# SwipingCard.net
KiCad netlist of a schematic drawn in Altium Designer
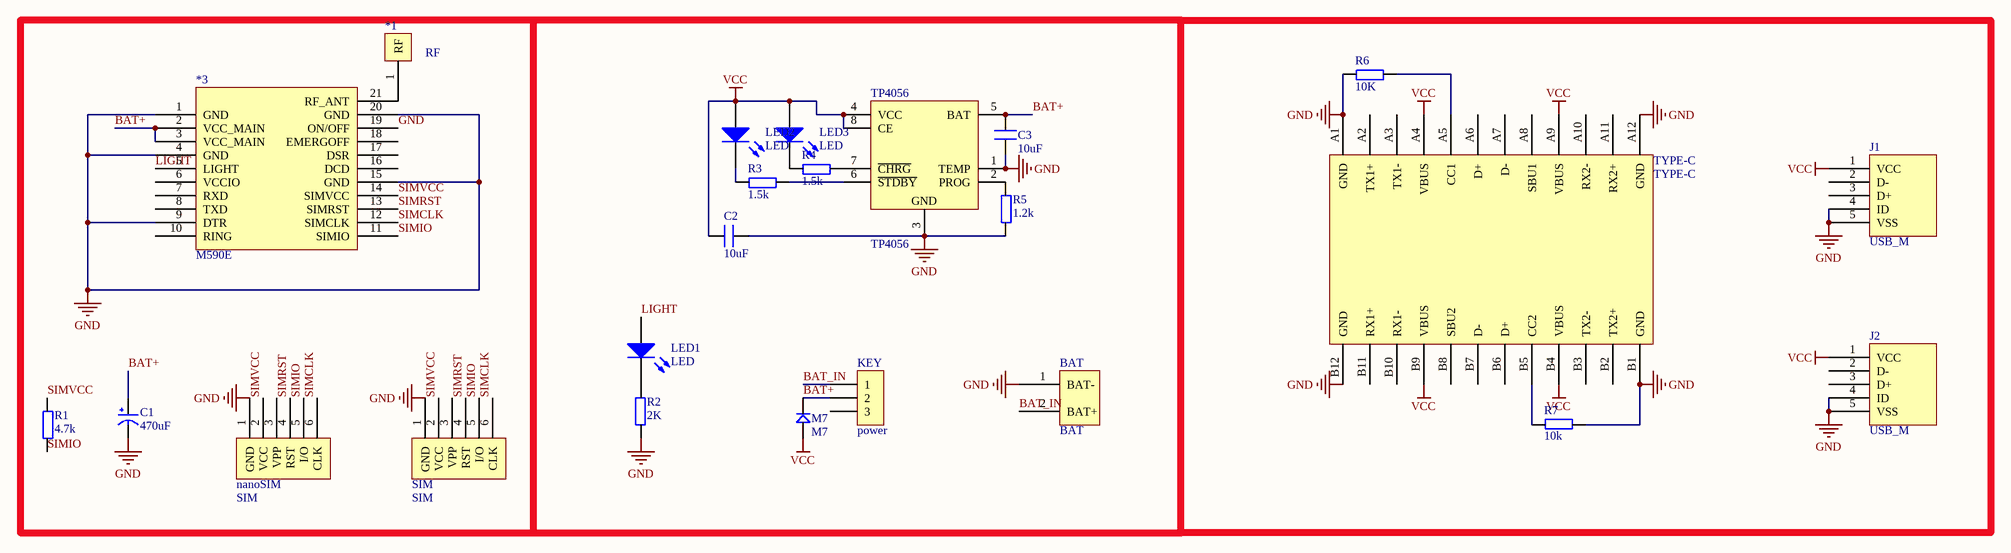
[diagram p0: SwipingCard.SchDoc]

(export (version "E")
  (design (tool "Eeschema 10.0.6"))
  (components
    (comp (ref "*1") (value "RF") (footprint "harder1x1") (libsource (lib "SwipingCard") (part "harder1x1")))
    (comp (ref "*3") (value "M590E") (footprint "M590E") (libsource (lib "SwipingCard") (part "M590E")))
    (comp (ref "BAT") (value "BAT") (footprint "HEADER1*2") (libsource (lib "SwipingCard") (part "BAT")))
    (comp (ref "C1") (value "470uF") (footprint "1206") (libsource (lib "SwipingCard") (part "C")))
    (comp (ref "C2") (value "10uF") (footprint "0603") (libsource (lib "SwipingCard") (part "cap")))
    (comp (ref "C3") (value "10uF") (footprint "0603") (libsource (lib "SwipingCard") (part "cap")))
    (comp (ref "J1")
      (value "USB_M")
      (footprint "USB_MICRO")
      (description "MicroUSB接口")
      (libsource (lib "SwipingCard") (part "USB_M"))
    )
    (comp (ref "J2")
      (value "USB_M")
      (footprint "micro")
      (description "MicroUSB接口")
      (libsource (lib "SwipingCard") (part "USB_M"))
    )
    (comp (ref "KEY") (value "power") (footprint "HARDER1*3") (libsource (lib "SwipingCard") (part "power")))
    (comp (ref "LED1") (value "LED") (footprint "0603") (libsource (lib "SwipingCard") (part "LED")))
    (comp (ref "LED2") (value "LED") (footprint "0603") (libsource (lib "SwipingCard") (part "LED")))
    (comp (ref "LED3") (value "LED") (footprint "0603") (libsource (lib "SwipingCard") (part "LED")))
    (comp (ref "M7") (value "M7") (footprint "DIODE_SOP") (libsource (lib "SwipingCard") (part "M7")))
    (comp (ref "nanoSIM") (value "SIM") (footprint "nanoSIM") (libsource (lib "SwipingCard") (part "SIM")))
    (comp (ref "R1") (value "4.7k") (footprint "0603") (libsource (lib "SwipingCard") (part "R")))
    (comp (ref "R2") (value "2K") (footprint "0603") (libsource (lib "SwipingCard") (part "R")))
    (comp (ref "R3") (value "1.5k") (footprint "0603") (libsource (lib "SwipingCard") (part "R")))
    (comp (ref "R4") (value "1.5k") (footprint "0603") (libsource (lib "SwipingCard") (part "R")))
    (comp (ref "R5") (value "1.2k") (footprint "0603") (libsource (lib "SwipingCard") (part "R")))
    (comp (ref "R6") (value "10K") (footprint "0603") (libsource (lib "SwipingCard") (part "R")))
    (comp (ref "R7") (value "10k") (footprint "0603") (libsource (lib "SwipingCard") (part "R")))
    (comp (ref "SIM") (value "SIM") (footprint "microSIM") (libsource (lib "SwipingCard") (part "SIM")))
    (comp (ref "TP4056")
      (value "TP4056")
      (footprint "TP4056")
      (libsource (lib "SwipingCard") (part "TP4056"))
    )
    (comp (ref "TYPE-C")
      (value "TYPE-C")
      (footprint "TYPE-C")
      (libsource (lib "SwipingCard") (part "TYPE-C"))
    )
  )
  (nets
    (net (code "1") (name "/BAT+") (class "Default")
      (node (ref "*3") (pin "2") (pinfunction "VCC_MAIN_2") (pintype "passive"))
      (node (ref "*3") (pin "3") (pinfunction "VCC_MAIN_3") (pintype "passive"))
      (node (ref "C1") (pin "1") (pinfunction "VCC_1") (pintype "passive"))
      (node (ref "C3") (pin "2") (pintype "passive"))
      (node (ref "KEY") (pin "2") (pinfunction "2_2") (pintype "passive"))
      (node (ref "M7") (pin "2") (pintype "passive"))
      (node (ref "TP4056") (pin "5") (pinfunction "BAT_5") (pintype "passive"))
    )
    (net (code "2") (name "/BAT_IN") (class "Default")
      (node (ref "BAT") (pin "2") (pinfunction "BAT+_2") (pintype "passive"))
      (node (ref "KEY") (pin "1") (pinfunction "1_1") (pintype "passive"))
    )
    (net (code "3") (name "/LIGHT") (class "Default")
      (node (ref "*3") (pin "5") (pinfunction "LIGHT_5") (pintype "passive"))
      (node (ref "LED1") (pin "1") (pinfunction "A_1") (pintype "passive"))
    )
    (net (code "4") (name "/SIMCLK") (class "Default")
      (node (ref "*3") (pin "12") (pinfunction "SIMCLK_12") (pintype "passive"))
      (node (ref "SIM") (pin "6") (pinfunction "CLK_6") (pintype "passive"))
      (node (ref "nanoSIM") (pin "6") (pinfunction "CLK_6") (pintype "passive"))
    )
    (net (code "5") (name "/SIMIO") (class "Default")
      (node (ref "*3") (pin "11") (pinfunction "SIMIO_11") (pintype "passive"))
      (node (ref "R1") (pin "1") (pintype "passive"))
      (node (ref "SIM") (pin "5") (pinfunction "I/O_5") (pintype "passive"))
      (node (ref "nanoSIM") (pin "5") (pinfunction "I/O_5") (pintype "passive"))
    )
    (net (code "6") (name "/SIMRST") (class "Default")
      (node (ref "*3") (pin "13") (pinfunction "SIMRST_13") (pintype "passive"))
      (node (ref "SIM") (pin "4") (pinfunction "RST_4") (pintype "passive"))
      (node (ref "nanoSIM") (pin "4") (pinfunction "RST_4") (pintype "passive"))
    )
    (net (code "7") (name "/SIMVCC") (class "Default")
      (node (ref "*3") (pin "14") (pinfunction "SIMVCC_14") (pintype "passive"))
      (node (ref "R1") (pin "2") (pintype "passive"))
      (node (ref "SIM") (pin "2") (pinfunction "VCC_2") (pintype "passive"))
      (node (ref "nanoSIM") (pin "2") (pinfunction "VCC_2") (pintype "passive"))
    )
    (net (code "8") (name "GND") (class "Default")
      (node (ref "*3") (pin "1") (pinfunction "GND_1") (pintype "passive"))
      (node (ref "*3") (pin "15") (pinfunction "GND_15") (pintype "passive"))
      (node (ref "*3") (pin "19") (pinfunction "ON/OFF_19") (pintype "passive"))
      (node (ref "*3") (pin "20") (pinfunction "GND_20") (pintype "passive"))
      (node (ref "*3") (pin "4") (pinfunction "GND_4") (pintype "passive"))
      (node (ref "*3") (pin "9") (pinfunction "DTR_9") (pintype "passive"))
      (node (ref "BAT") (pin "1") (pinfunction "BAT-_1") (pintype "passive"))
      (node (ref "C1") (pin "2") (pinfunction "GND_2") (pintype "passive"))
      (node (ref "C2") (pin "2") (pintype "passive"))
      (node (ref "C3") (pin "1") (pintype "passive"))
      (node (ref "J1") (pin "4") (pinfunction "ID_4") (pintype "passive"))
      (node (ref "J1") (pin "5") (pinfunction "VSS_5") (pintype "passive"))
      (node (ref "J2") (pin "4") (pinfunction "ID_4") (pintype "passive"))
      (node (ref "J2") (pin "5") (pinfunction "VSS_5") (pintype "passive"))
      (node (ref "R2") (pin "2") (pintype "passive"))
      (node (ref "R5") (pin "1") (pintype "passive"))
      (node (ref "R6") (pin "1") (pintype "passive"))
      (node (ref "R7") (pin "1") (pintype "passive"))
      (node (ref "SIM") (pin "1") (pinfunction "GND_1") (pintype "passive"))
      (node (ref "TP4056") (pin "1") (pinfunction "TEMP_1") (pintype "passive"))
      (node (ref "TP4056") (pin "3") (pinfunction "GND_3") (pintype "passive"))
      (node (ref "TYPE-C") (pin "A1") (pinfunction "GND_A1") (pintype "passive"))
      (node (ref "TYPE-C") (pin "A12") (pinfunction "GND_A12") (pintype "passive"))
      (node (ref "TYPE-C") (pin "B1") (pinfunction "GND_B1") (pintype "passive"))
      (node (ref "TYPE-C") (pin "B12") (pinfunction "GND_B12") (pintype "passive"))
      (node (ref "nanoSIM") (pin "1") (pinfunction "GND_1") (pintype "passive"))
    )
    (net (code "9") (name "Net-(*1-RF)") (class "Default")
      (node (ref "*1") (pin "1") (pinfunction "RF_1") (pintype "passive"))
      (node (ref "*3") (pin "21") (pinfunction "RF_ANT_21") (pintype "passive"))
    )
    (net (code "10") (name "Net-(LED1-K)") (class "Default")
      (node (ref "LED1") (pin "2") (pinfunction "K_2") (pintype "passive"))
      (node (ref "R2") (pin "1") (pintype "passive"))
    )
    (net (code "11") (name "Net-(LED2-K)") (class "Default")
      (node (ref "LED2") (pin "2") (pinfunction "K_2") (pintype "passive"))
      (node (ref "R3") (pin "1") (pintype "passive"))
    )
    (net (code "12") (name "Net-(LED3-K)") (class "Default")
      (node (ref "LED3") (pin "2") (pinfunction "K_2") (pintype "passive"))
      (node (ref "R4") (pin "1") (pintype "passive"))
    )
    (net (code "13") (name "Net-(TP4056-PROG)") (class "Default")
      (node (ref "R5") (pin "2") (pintype "passive"))
      (node (ref "TP4056") (pin "2") (pinfunction "PROG_2") (pintype "passive"))
    )
    (net (code "14") (name "Net-(TP4056-~{CHRG})") (class "Default")
      (node (ref "R4") (pin "2") (pintype "passive"))
      (node (ref "TP4056") (pin "7") (pinfunction "~{CHRG}_7") (pintype "passive"))
    )
    (net (code "15") (name "Net-(TP4056-~{STDBY})") (class "Default")
      (node (ref "R3") (pin "2") (pintype "passive"))
      (node (ref "TP4056") (pin "6") (pinfunction "~{STDBY}_6") (pintype "passive"))
    )
    (net (code "16") (name "Net-(TYPE-C-CC1)") (class "Default")
      (node (ref "R6") (pin "2") (pintype "passive"))
      (node (ref "TYPE-C") (pin "A5") (pinfunction "CC1_A5") (pintype "passive"))
    )
    (net (code "17") (name "Net-(TYPE-C-CC2)") (class "Default")
      (node (ref "R7") (pin "2") (pintype "passive"))
      (node (ref "TYPE-C") (pin "B5") (pinfunction "CC2_B5") (pintype "passive"))
    )
    (net (code "18") (name "VCC") (class "Default")
      (node (ref "C2") (pin "1") (pintype "passive"))
      (node (ref "J1") (pin "1") (pinfunction "VCC_1") (pintype "passive"))
      (node (ref "J2") (pin "1") (pinfunction "VCC_1") (pintype "passive"))
      (node (ref "LED2") (pin "1") (pinfunction "A_1") (pintype "passive"))
      (node (ref "LED3") (pin "1") (pinfunction "A_1") (pintype "passive"))
      (node (ref "M7") (pin "1") (pintype "passive"))
      (node (ref "TP4056") (pin "4") (pinfunction "VCC_4") (pintype "passive"))
      (node (ref "TP4056") (pin "8") (pinfunction "CE_8") (pintype "passive"))
      (node (ref "TYPE-C") (pin "A4") (pinfunction "VBUS_A4") (pintype "passive"))
      (node (ref "TYPE-C") (pin "A9") (pinfunction "VBUS_A9") (pintype "passive"))
      (node (ref "TYPE-C") (pin "B4") (pinfunction "VBUS_B4") (pintype "passive"))
      (node (ref "TYPE-C") (pin "B9") (pinfunction "VBUS_B9") (pintype "passive"))
    )
    (net (code "19") (name "unconnected-(*3-DCD-Pad16)") (class "Default")
      (node (ref "*3") (pin "16") (pinfunction "DCD_16") (pintype "passive"))
    )
    (net (code "20") (name "unconnected-(*3-DSR-Pad17)") (class "Default")
      (node (ref "*3") (pin "17") (pinfunction "DSR_17") (pintype "passive"))
    )
    (net (code "21") (name "unconnected-(*3-EMERGOFF-Pad18)") (class "Default")
      (node (ref "*3") (pin "18") (pinfunction "EMERGOFF_18") (pintype "passive"))
    )
    (net (code "22") (name "unconnected-(*3-RING-Pad10)") (class "Default")
      (node (ref "*3") (pin "10") (pinfunction "RING_10") (pintype "passive"))
    )
    (net (code "23") (name "unconnected-(*3-RXD-Pad7)") (class "Default")
      (node (ref "*3") (pin "7") (pinfunction "RXD_7") (pintype "passive"))
    )
    (net (code "24") (name "unconnected-(*3-TXD-Pad8)") (class "Default")
      (node (ref "*3") (pin "8") (pinfunction "TXD_8") (pintype "passive"))
    )
    (net (code "25") (name "unconnected-(*3-VCCIO-Pad6)") (class "Default")
      (node (ref "*3") (pin "6") (pinfunction "VCCIO_6") (pintype "passive"))
    )
    (net (code "26") (name "unconnected-(J1-D+-Pad3)") (class "Default")
      (node (ref "J1") (pin "3") (pinfunction "D+_3") (pintype "passive"))
    )
    (net (code "27") (name "unconnected-(J1-D--Pad2)") (class "Default")
      (node (ref "J1") (pin "2") (pinfunction "D-_2") (pintype "passive"))
    )
    (net (code "28") (name "unconnected-(J2-D+-Pad3)") (class "Default")
      (node (ref "J2") (pin "3") (pinfunction "D+_3") (pintype "passive"))
    )
    (net (code "29") (name "unconnected-(J2-D--Pad2)") (class "Default")
      (node (ref "J2") (pin "2") (pinfunction "D-_2") (pintype "passive"))
    )
    (net (code "30") (name "unconnected-(KEY-Pad3)") (class "Default")
      (node (ref "KEY") (pin "3") (pinfunction "3_3") (pintype "passive"))
    )
    (net (code "31") (name "unconnected-(SIM-VPP-Pad3)") (class "Default")
      (node (ref "SIM") (pin "3") (pinfunction "VPP_3") (pintype "passive"))
    )
    (net (code "32") (name "unconnected-(TYPE-C-D+-PadA6)") (class "Default")
      (node (ref "TYPE-C") (pin "A6") (pinfunction "D+_A6") (pintype "passive"))
    )
    (net (code "33") (name "unconnected-(TYPE-C-D+-PadB6)") (class "Default")
      (node (ref "TYPE-C") (pin "B6") (pinfunction "D+_B6") (pintype "passive"))
    )
    (net (code "34") (name "unconnected-(TYPE-C-D--PadA7)") (class "Default")
      (node (ref "TYPE-C") (pin "A7") (pinfunction "D-_A7") (pintype "passive"))
    )
    (net (code "35") (name "unconnected-(TYPE-C-D--PadB7)") (class "Default")
      (node (ref "TYPE-C") (pin "B7") (pinfunction "D-_B7") (pintype "passive"))
    )
    (net (code "36") (name "unconnected-(TYPE-C-RX1+-PadB11)") (class "Default")
      (node (ref "TYPE-C") (pin "B11") (pinfunction "RX1+_B11") (pintype "passive"))
    )
    (net (code "37") (name "unconnected-(TYPE-C-RX1--PadB10)") (class "Default")
      (node (ref "TYPE-C") (pin "B10") (pinfunction "RX1-_B10") (pintype "passive"))
    )
    (net (code "38") (name "unconnected-(TYPE-C-RX2+-PadA11)") (class "Default")
      (node (ref "TYPE-C") (pin "A11") (pinfunction "RX2+_A11") (pintype "passive"))
    )
    (net (code "39") (name "unconnected-(TYPE-C-RX2--PadA10)") (class "Default")
      (node (ref "TYPE-C") (pin "A10") (pinfunction "RX2-_A10") (pintype "passive"))
    )
    (net (code "40") (name "unconnected-(TYPE-C-SBU1-PadA8)") (class "Default")
      (node (ref "TYPE-C") (pin "A8") (pinfunction "SBU1_A8") (pintype "passive"))
    )
    (net (code "41") (name "unconnected-(TYPE-C-SBU2-PadB8)") (class "Default")
      (node (ref "TYPE-C") (pin "B8") (pinfunction "SBU2_B8") (pintype "passive"))
    )
    (net (code "42") (name "unconnected-(TYPE-C-TX1+-PadA2)") (class "Default")
      (node (ref "TYPE-C") (pin "A2") (pinfunction "TX1+_A2") (pintype "passive"))
    )
    (net (code "43") (name "unconnected-(TYPE-C-TX1--PadA3)") (class "Default")
      (node (ref "TYPE-C") (pin "A3") (pinfunction "TX1-_A3") (pintype "passive"))
    )
    (net (code "44") (name "unconnected-(TYPE-C-TX2+-PadB2)") (class "Default")
      (node (ref "TYPE-C") (pin "B2") (pinfunction "TX2+_B2") (pintype "passive"))
    )
    (net (code "45") (name "unconnected-(TYPE-C-TX2--PadB3)") (class "Default")
      (node (ref "TYPE-C") (pin "B3") (pinfunction "TX2-_B3") (pintype "passive"))
    )
    (net (code "46") (name "unconnected-(nanoSIM-VPP-Pad3)") (class "Default")
      (node (ref "nanoSIM") (pin "3") (pinfunction "VPP_3") (pintype "passive"))
    )
  )
)
